# Schematic.net
KiCad netlist of a schematic drawn in EAGLE
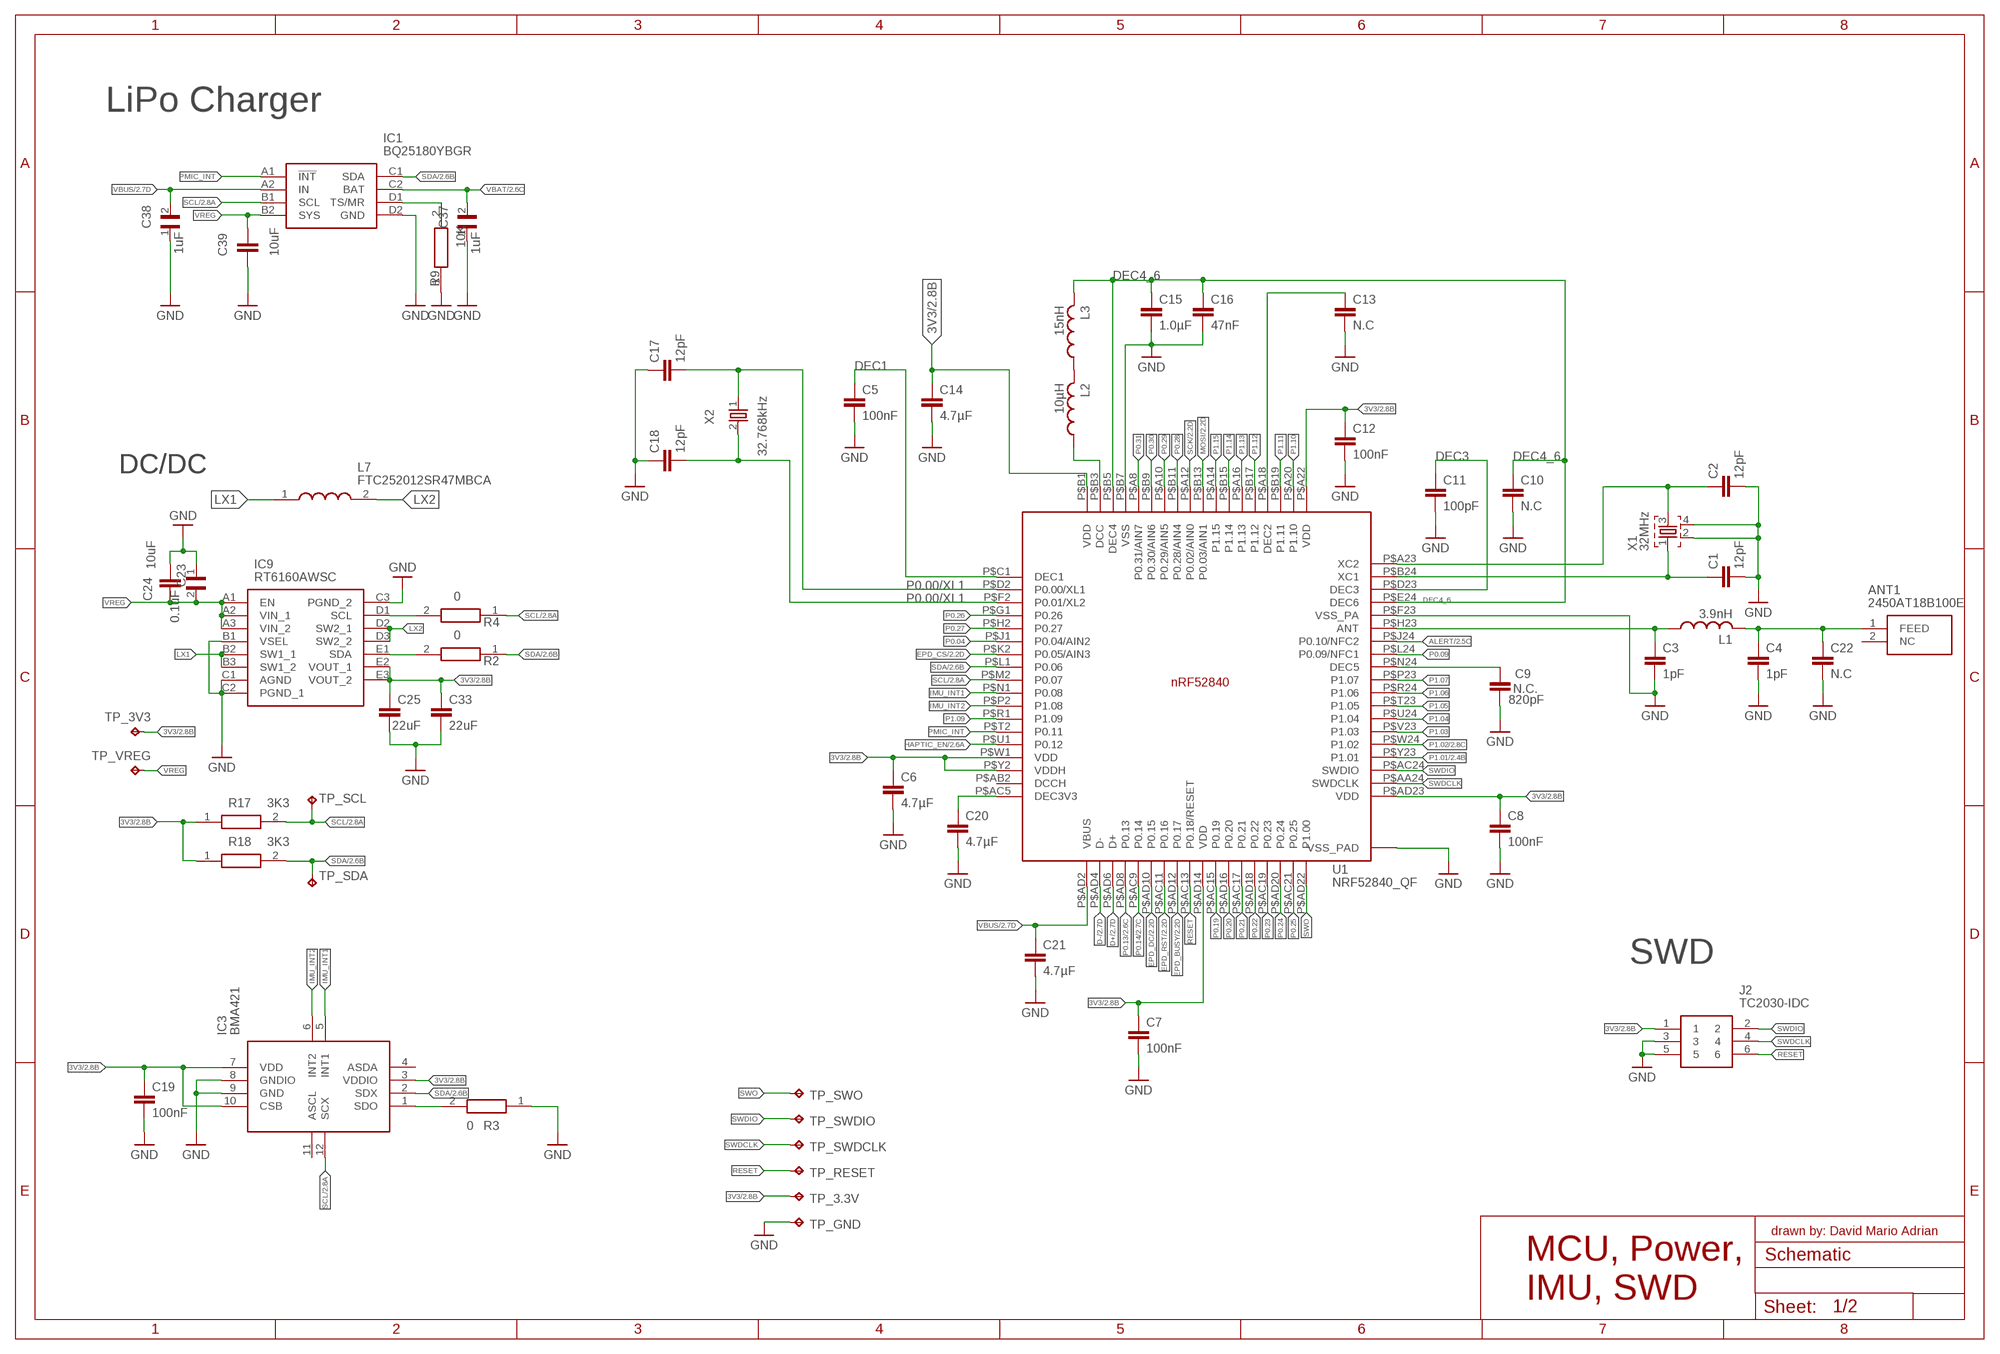
[diagram p0: schematic, sheet 1]
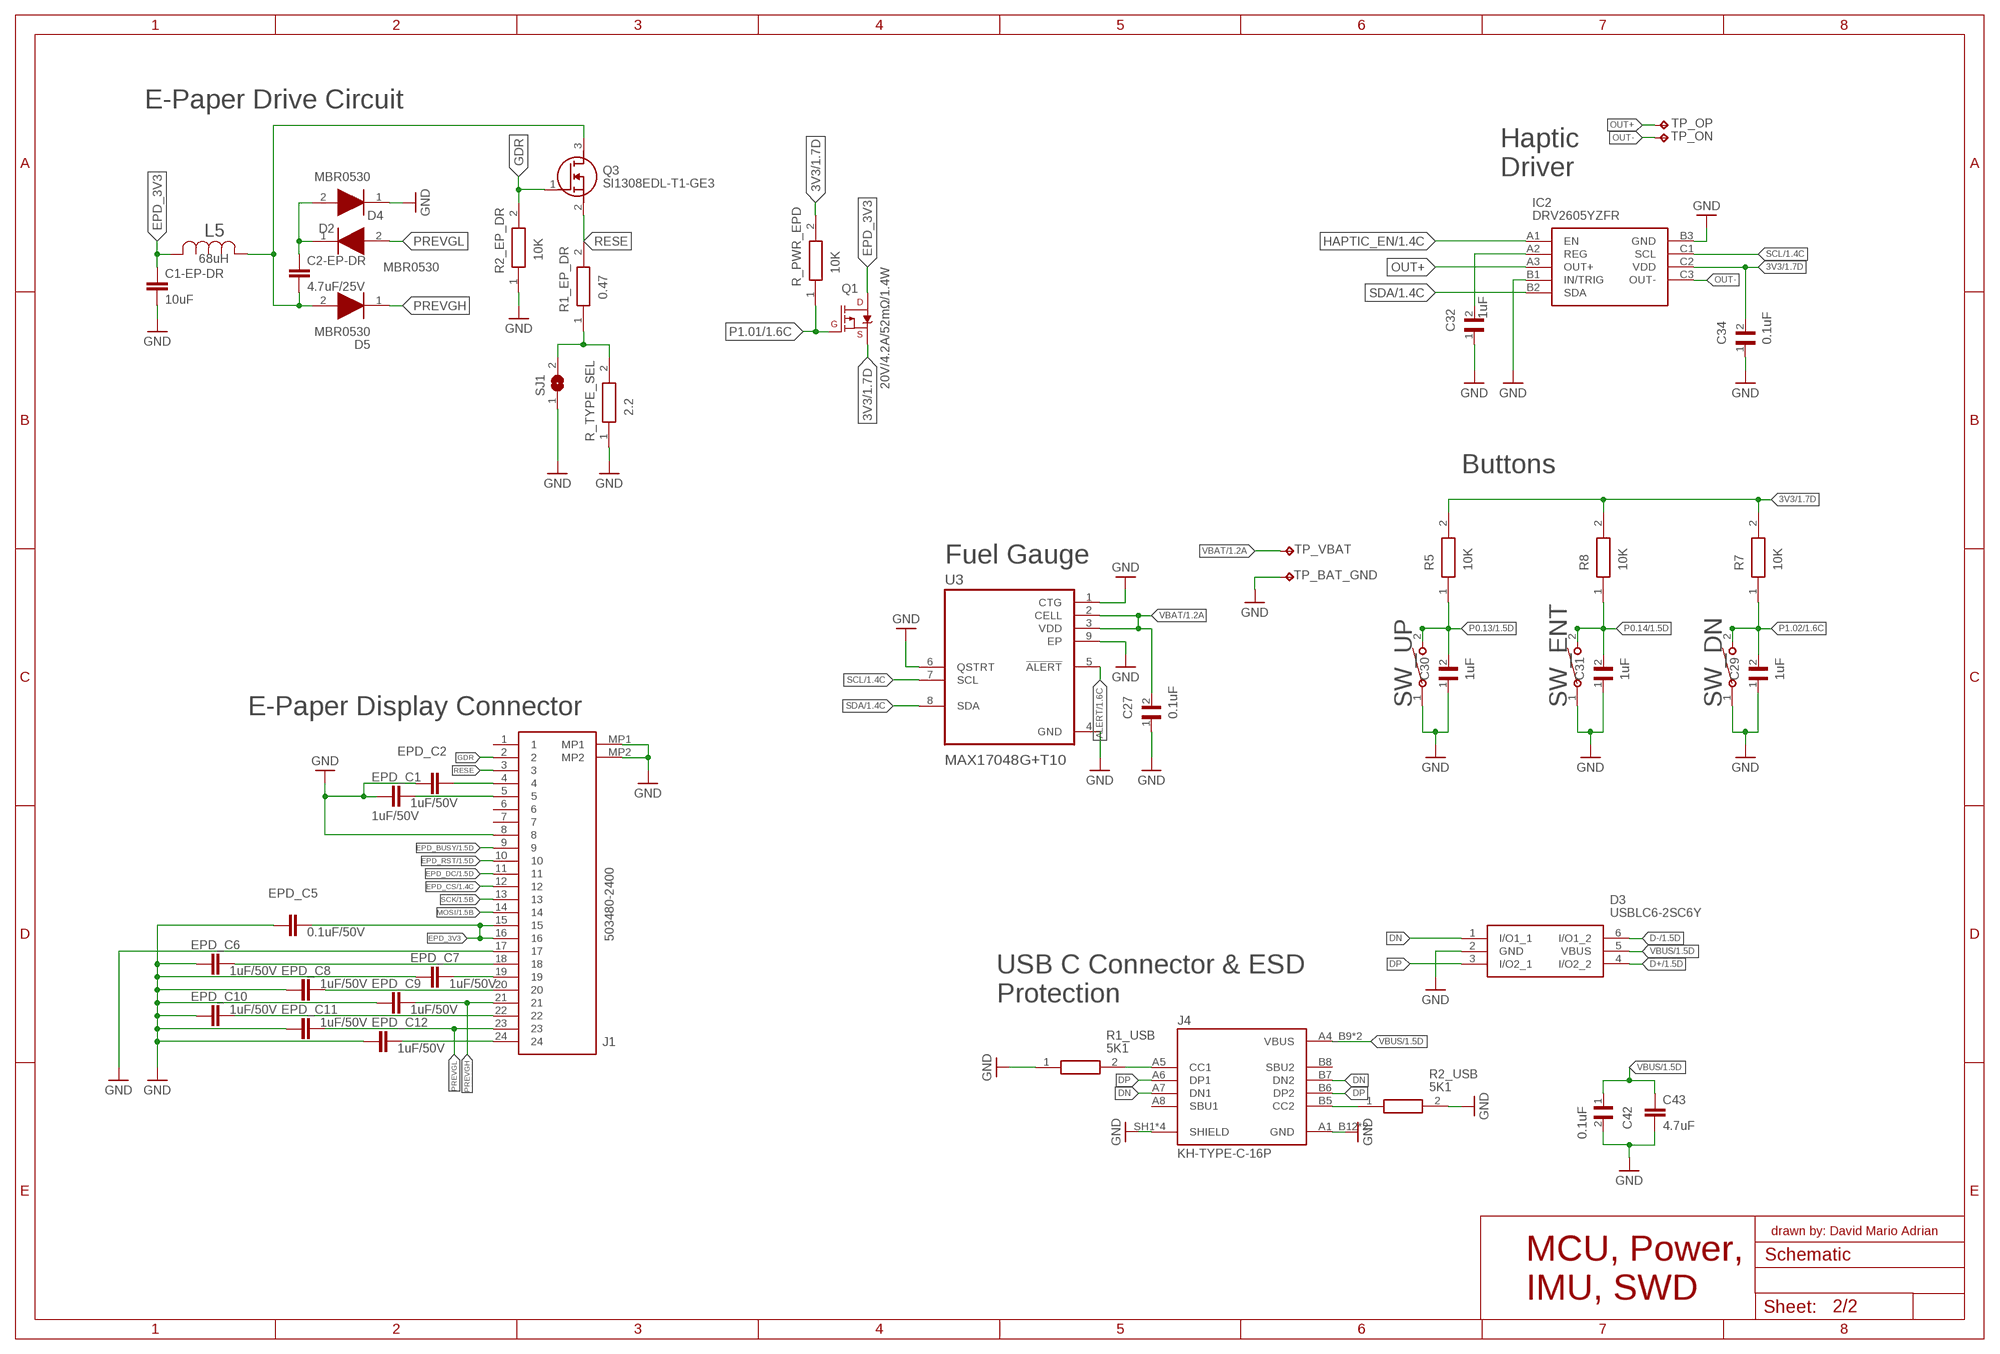
[diagram p1: schematic, sheet 2]

(export (version "E")
  (design (tool "Eeschema 10.0.6"))
  (components
    (comp (ref "C1-EP-DR")
      (value "10uF")
      (footprint "eagle-import:NORDIC_NRF_3_RESC0603_L")
      (libsource (lib "eagle-import") (part "NORDIC_NRF_3_CAPACITOR_0603_L"))
    )
    (comp (ref "C2-EP-DR")
      (value "4.7uF/25V")
      (footprint "eagle-import:NORDIC_NRF_3_RESC0603_L")
      (libsource (lib "eagle-import") (part "NORDIC_NRF_3_CAPACITOR_0603_L"))
    )
    (comp (ref "C27")
      (value "0.1uF")
      (footprint "eagle-import:GRM011R60J152KE01L_2_CAPC0201X13N")
      (fields (field (name "MF") "Murata") (field (name "MP") "GRM011R60J152KE01L"))
      (libsource (lib "eagle-import") (part "GRM011R60J152KE01L_2_GRM011R60J152KE01L"))
    )
    (comp (ref "C29")
      (value "1uF")
      (footprint "eagle-import:GRM011R60J152KE01L_2_CAPC0201X13N")
      (fields (field (name "MF") "Murata") (field (name "MP") "GRM011R60J152KE01L"))
      (libsource (lib "eagle-import") (part "GRM011R60J152KE01L_2_GRM011R60J152KE01L"))
    )
    (comp (ref "C30")
      (value "1uF")
      (footprint "eagle-import:GRM011R60J152KE01L_2_CAPC0201X13N")
      (fields (field (name "MF") "Murata") (field (name "MP") "GRM011R60J152KE01L"))
      (libsource (lib "eagle-import") (part "GRM011R60J152KE01L_2_GRM011R60J152KE01L"))
    )
    (comp (ref "C31")
      (value "1uF")
      (footprint "eagle-import:GRM011R60J152KE01L_2_CAPC0201X13N")
      (fields (field (name "MF") "Murata") (field (name "MP") "GRM011R60J152KE01L"))
      (libsource (lib "eagle-import") (part "GRM011R60J152KE01L_2_GRM011R60J152KE01L"))
    )
    (comp (ref "C32")
      (value "1uF")
      (footprint "eagle-import:GRM011R60J152KE01L_2_CAPC0201X13N")
      (fields (field (name "MF") "Murata") (field (name "MP") "GRM011R60J152KE01L"))
      (libsource (lib "eagle-import") (part "GRM011R60J152KE01L_2_GRM011R60J152KE01L"))
    )
    (comp (ref "C34")
      (value "0.1uF")
      (footprint "eagle-import:GRM011R60J152KE01L_2_CAPC0201X13N")
      (fields (field (name "MF") "Murata") (field (name "MP") "GRM011R60J152KE01L"))
      (libsource (lib "eagle-import") (part "GRM011R60J152KE01L_2_GRM011R60J152KE01L"))
    )
    (comp (ref "C42")
      (value "0.1uF")
      (footprint "eagle-import:GRM011R60J152KE01L_2_CAPC0201X13N")
      (fields (field (name "MF") "Murata") (field (name "MP") "GRM011R60J152KE01L"))
      (libsource (lib "eagle-import") (part "GRM011R60J152KE01L_2_GRM011R60J152KE01L"))
    )
    (comp (ref "C43")
      (value "4.7uF")
      (footprint "eagle-import:PERFECT_0402_0402")
      (libsource (lib "eagle-import") (part "PERFECT_0402_CAP_0402"))
    )
    (comp (ref "D2")
      (value "MBR0530")
      (footprint "eagle-import:ESP32_C6_LIBRARY_5_SOD3716X135N")
      (fields (field (name "MF") "ON Semiconductor"))
      (libsource (lib "eagle-import") (part "ESP32_C6_LIBRARY_5_MBR0530"))
    )
    (comp (ref "D3")
      (value "USBLC6-2SC6Y")
      (footprint "eagle-import:ESP32_C6_LIBRARY_3_SOT95P280X145-6N")
      (fields (field (name "MF") "STMicroelectronics"))
      (libsource (lib "eagle-import") (part "ESP32_C6_LIBRARY_3_USBLC6-2SC6Y"))
    )
    (comp (ref "D4")
      (value "MBR0530")
      (footprint "eagle-import:ESP32_C6_LIBRARY_5_SOD3716X135N")
      (fields (field (name "MF") "ON Semiconductor"))
      (libsource (lib "eagle-import") (part "ESP32_C6_LIBRARY_5_MBR0530"))
    )
    (comp (ref "D5")
      (value "MBR0530")
      (footprint "eagle-import:ESP32_C6_LIBRARY_5_SOD3716X135N")
      (fields (field (name "MF") "ON Semiconductor"))
      (libsource (lib "eagle-import") (part "ESP32_C6_LIBRARY_5_MBR0530"))
    )
    (comp (ref "EPD_C1")
      (value "1uF/50V")
      (footprint "eagle-import:PERFECT_0402_0402")
      (libsource (lib "eagle-import") (part "PERFECT_0402_CAP_0402"))
    )
    (comp (ref "EPD_C2")
      (value "1uF/50V")
      (footprint "eagle-import:PERFECT_0402_0402")
      (libsource (lib "eagle-import") (part "PERFECT_0402_CAP_0402"))
    )
    (comp (ref "EPD_C5")
      (value "0.1uF/50V")
      (footprint "eagle-import:NORDIC_NRF_3_RESC0201_L")
      (libsource (lib "eagle-import") (part "NORDIC_NRF_3_CAPACITOR_0201_L"))
    )
    (comp (ref "EPD_C6")
      (value "1uF/50V")
      (footprint "eagle-import:PERFECT_0402_0402")
      (libsource (lib "eagle-import") (part "PERFECT_0402_CAP_0402"))
    )
    (comp (ref "EPD_C7")
      (value "1uF/50V")
      (footprint "eagle-import:PERFECT_0402_0402")
      (libsource (lib "eagle-import") (part "PERFECT_0402_CAP_0402"))
    )
    (comp (ref "EPD_C8")
      (value "1uF/50V")
      (footprint "eagle-import:PERFECT_0402_0402")
      (libsource (lib "eagle-import") (part "PERFECT_0402_CAP_0402"))
    )
    (comp (ref "EPD_C9")
      (value "1uF/50V")
      (footprint "eagle-import:PERFECT_0402_0402")
      (libsource (lib "eagle-import") (part "PERFECT_0402_CAP_0402"))
    )
    (comp (ref "EPD_C10")
      (value "1uF/50V")
      (footprint "eagle-import:PERFECT_0402_0402")
      (libsource (lib "eagle-import") (part "PERFECT_0402_CAP_0402"))
    )
    (comp (ref "EPD_C11")
      (value "1uF/50V")
      (footprint "eagle-import:PERFECT_0402_0402")
      (libsource (lib "eagle-import") (part "PERFECT_0402_CAP_0402"))
    )
    (comp (ref "EPD_C12")
      (value "1uF/50V")
      (footprint "eagle-import:PERFECT_0402_0402")
      (libsource (lib "eagle-import") (part "PERFECT_0402_CAP_0402"))
    )
    (comp (ref "IC2")
      (value "DRV2605YZFR")
      (footprint "eagle-import:DRV2605YZFR_BGA9C50P3X3_144X144X62")
      (libsource (lib "eagle-import") (part "DRV2605YZFR_DRV2605YZFR"))
    )
    (comp (ref "J1")
      (value "503480-2400")
      (footprint "eagle-import:503480-2400_5034802400")
      (fields (field (name "MOUSER_PART_NUMBER") "538-503480-2400"))
      (libsource (lib "eagle-import") (part "503480-2400_503480-2400"))
    )
    (comp (ref "J4")
      (value "KH-TYPE-C-16P")
      (footprint "eagle-import:KH-TYPE-C-16P_KINGHELM_KH-TYPE-C-16P")
      (fields (field (name "MF") "kinghelm"))
      (libsource (lib "eagle-import") (part "KH-TYPE-C-16P_KH-TYPE-C-16P"))
    )
    (comp (ref "L5")
      (value "68uH")
      (footprint "eagle-import:ESP32_C6_LIBRARY_2_IND_4828-WE-TPC_WRE")
      (fields
        (field (name "MANUFACTURER_PART_NUMBER") "744043680")
        (field (name "COPYRIGHT") "Copyright (C) 2024 Ultra Librarian. All rights reserved.")
      )
      (libsource (lib "eagle-import") (part "ESP32_C6_LIBRARY_2_744043680IND_4828-WE-TPC_WRE"))
    )
    (comp (ref "Q1")
      (value "20V/4.2A/52mΩ/1.4W")
      (footprint "eagle-import:ESP32_C6_LIBRARY_4_ESP32_C6_LIBRARY_4_ESP32_C6_LIBRARY_4_ESP32_C6_LIBRARY_4_ESP32_WROVER_SPARKFUN-DISCRETESEMI_SOT23-3")
      (libsource (lib "eagle-import") (part "ESP32_C6_LIBRARY_4_ESP32_WROVER_SPARKFUN-DISCRETESEMI_MOSFET_PCH-DMG2305UX-7"))
    )
    (comp (ref "Q3")
      (value "SI1308EDL-T1-GE3")
      (footprint "eagle-import:ESP32_C6_LIBRARY_6_SOT65P210X110-3N")
      (fields (field (name "MF") "Vishay Siliconix"))
      (libsource (lib "eagle-import") (part "ESP32_C6_LIBRARY_6_SI1308EDL-T1-GE3"))
    )
    (comp (ref "R1_EP_DR")
      (value "0.47")
      (footprint "eagle-import:CPF0201D7K68C1_0201")
      (libsource (lib "eagle-import") (part "CPF0201D7K68C1_CPF0201D7K68C1"))
    )
    (comp (ref "R1_USB")
      (value "5K1")
      (footprint "eagle-import:CPF0201D7K68C1_0201")
      (libsource (lib "eagle-import") (part "CPF0201D7K68C1_CPF0201D7K68C1"))
    )
    (comp (ref "R2_EP_DR")
      (value "10K")
      (footprint "eagle-import:CPF0201D7K68C1_0201")
      (libsource (lib "eagle-import") (part "CPF0201D7K68C1_CPF0201D7K68C1"))
    )
    (comp (ref "R2_USB")
      (value "5K1")
      (footprint "eagle-import:CPF0201D7K68C1_0201")
      (libsource (lib "eagle-import") (part "CPF0201D7K68C1_CPF0201D7K68C1"))
    )
    (comp (ref "R5")
      (value "10K")
      (footprint "eagle-import:CPF0201D7K68C1_0201")
      (libsource (lib "eagle-import") (part "CPF0201D7K68C1_CPF0201D7K68C1"))
    )
    (comp (ref "R7")
      (value "10K")
      (footprint "eagle-import:CPF0201D7K68C1_0201")
      (libsource (lib "eagle-import") (part "CPF0201D7K68C1_CPF0201D7K68C1"))
    )
    (comp (ref "R8")
      (value "10K")
      (footprint "eagle-import:CPF0201D7K68C1_0201")
      (libsource (lib "eagle-import") (part "CPF0201D7K68C1_CPF0201D7K68C1"))
    )
    (comp (ref "R_PWR_EPD")
      (value "10K")
      (footprint "eagle-import:CPF0201D7K68C1_0201")
      (libsource (lib "eagle-import") (part "CPF0201D7K68C1_CPF0201D7K68C1"))
    )
    (comp (ref "R_TYPE_SEL")
      (value "2.2")
      (footprint "eagle-import:CPF0201D7K68C1_0201")
      (libsource (lib "eagle-import") (part "CPF0201D7K68C1_CPF0201D7K68C1"))
    )
    (comp (ref "SJ1")
      (value "ESP32_C6_LIBRARY_7_JUMPER_SJ")
      (footprint "eagle-import:ESP32_C6_LIBRARY_7_JUMPER_SJ")
      (libsource (lib "eagle-import") (part "ESP32_C6_LIBRARY_7_JUMPER_SJ"))
    )
    (comp (ref "SW_DN")
      (value "2025-10-22_07-23-44_LIBRARY_EVP-AKE31ASW_EVP-AKE31A_PAN")
      (footprint "eagle-import:2025-10-22_07-23-44_LIBRARY_SW_EVP-AKE31A_PAN")
      (fields
        (field (name "MANUFACTURER_PART_NUMBER") "EVP-AKE31A")
        (field (name "COPYRIGHT") "Copyright (C) 2025 Ultra Librarian. All rights reserved.")
      )
      (libsource (lib "eagle-import") (part "2025-10-22_07-23-44_LIBRARY_EVP-AKE31ASW_EVP-AKE31A_PAN"))
    )
    (comp (ref "SW_ENT")
      (value "2025-10-22_07-23-44_LIBRARY_EVP-AKE31ASW_EVP-AKE31A_PAN")
      (footprint "eagle-import:2025-10-22_07-23-44_LIBRARY_SW_EVP-AKE31A_PAN")
      (fields
        (field (name "MANUFACTURER_PART_NUMBER") "EVP-AKE31A")
        (field (name "COPYRIGHT") "Copyright (C) 2025 Ultra Librarian. All rights reserved.")
      )
      (libsource (lib "eagle-import") (part "2025-10-22_07-23-44_LIBRARY_EVP-AKE31ASW_EVP-AKE31A_PAN"))
    )
    (comp (ref "SW_UP")
      (value "2025-10-22_07-23-44_LIBRARY_EVP-AKE31ASW_EVP-AKE31A_PAN")
      (footprint "eagle-import:2025-10-22_07-23-44_LIBRARY_SW_EVP-AKE31A_PAN")
      (fields
        (field (name "MANUFACTURER_PART_NUMBER") "EVP-AKE31A")
        (field (name "COPYRIGHT") "Copyright (C) 2025 Ultra Librarian. All rights reserved.")
      )
      (libsource (lib "eagle-import") (part "2025-10-22_07-23-44_LIBRARY_EVP-AKE31ASW_EVP-AKE31A_PAN"))
    )
    (comp (ref "TP_BAT_GND")
      (value "HECTOR_WATCH_1_TPTP20R")
      (footprint "eagle-import:HECTOR_WATCH_1_TP20R")
      (libsource (lib "eagle-import") (part "HECTOR_WATCH_1_TPTP20R"))
    )
    (comp (ref "TP_ON")
      (value "HECTOR_WATCH_1_TPTP20R")
      (footprint "eagle-import:HECTOR_WATCH_1_TP20R")
      (libsource (lib "eagle-import") (part "HECTOR_WATCH_1_TPTP20R"))
    )
    (comp (ref "TP_OP")
      (value "HECTOR_WATCH_1_TPTP20R")
      (footprint "eagle-import:HECTOR_WATCH_1_TP20R")
      (libsource (lib "eagle-import") (part "HECTOR_WATCH_1_TPTP20R"))
    )
    (comp (ref "TP_VBAT")
      (value "HECTOR_WATCH_1_TPTP20R")
      (footprint "eagle-import:HECTOR_WATCH_1_TP20R")
      (libsource (lib "eagle-import") (part "HECTOR_WATCH_1_TPTP20R"))
    )
    (comp (ref "U3")
      (value "MAX17048G+T10")
      (footprint "eagle-import:ESP32_C6_LIBRARY_SON50P200X200X80-9N")
      (fields (field (name "MF") "Analog Devices"))
      (libsource (lib "eagle-import") (part "ESP32_C6_LIBRARY_MAX17048G+T10"))
    )
    (comp (ref "ANT1")
      (value "2450AT18B100E")
      (footprint "eagle-import:2450AT18B100E_ANTC3216X140N")
      (fields (field (name "MOUSER_PART_NUMBER") "609-2450AT18B100E"))
      (libsource (lib "eagle-import") (part "2450AT18B100E_2450AT18B100E"))
    )
    (comp (ref "C1")
      (value "12pF")
      (footprint "eagle-import:NORDIC_NRF_3_RESC0201_L")
      (libsource (lib "eagle-import") (part "NORDIC_NRF_3_CAPACITOR_0201_L"))
    )
    (comp (ref "C2")
      (value "12pF")
      (footprint "eagle-import:NORDIC_NRF_3_RESC0201_L")
      (libsource (lib "eagle-import") (part "NORDIC_NRF_3_CAPACITOR_0201_L"))
    )
    (comp (ref "C3")
      (value "1pF")
      (footprint "eagle-import:NORDIC_NRF_3_RESC0201_L")
      (libsource (lib "eagle-import") (part "NORDIC_NRF_3_CAPACITOR_0201_L"))
    )
    (comp (ref "C4")
      (value "1pF")
      (footprint "eagle-import:NORDIC_NRF_3_RESC0201_L")
      (libsource (lib "eagle-import") (part "NORDIC_NRF_3_CAPACITOR_0201_L"))
    )
    (comp (ref "C5")
      (value "100nF")
      (footprint "eagle-import:NORDIC_NRF_3_RESC0201_L")
      (libsource (lib "eagle-import") (part "NORDIC_NRF_3_CAPACITOR_0201_L"))
    )
    (comp (ref "C6")
      (value "4.7µF")
      (footprint "eagle-import:PERFECT_0402_0402")
      (libsource (lib "eagle-import") (part "PERFECT_0402_CAP_0402"))
    )
    (comp (ref "C7")
      (value "100nF")
      (footprint "eagle-import:NORDIC_NRF_3_RESC0201_L")
      (libsource (lib "eagle-import") (part "NORDIC_NRF_3_CAPACITOR_0201_L"))
    )
    (comp (ref "C8")
      (value "100nF")
      (footprint "eagle-import:NORDIC_NRF_3_RESC0201_L")
      (libsource (lib "eagle-import") (part "NORDIC_NRF_3_CAPACITOR_0201_L"))
    )
    (comp (ref "C9")
      (value "820pF")
      (footprint "eagle-import:NORDIC_NRF_3_RESC0201_L")
      (libsource (lib "eagle-import") (part "NORDIC_NRF_3_CAPACITOR_0201_L"))
    )
    (comp (ref "C10")
      (value "N.C")
      (footprint "eagle-import:NORDIC_NRF_3_RESC0201_L")
      (libsource (lib "eagle-import") (part "NORDIC_NRF_3_CAPACITOR_0201_L"))
    )
    (comp (ref "C11")
      (value "100pF")
      (footprint "eagle-import:NORDIC_NRF_3_RESC0201_L")
      (libsource (lib "eagle-import") (part "NORDIC_NRF_3_CAPACITOR_0201_L"))
    )
    (comp (ref "C12")
      (value "100nF")
      (footprint "eagle-import:NORDIC_NRF_3_RESC0201_L")
      (libsource (lib "eagle-import") (part "NORDIC_NRF_3_CAPACITOR_0201_L"))
    )
    (comp (ref "C13")
      (value "N.C")
      (footprint "eagle-import:NORDIC_NRF_3_RESC0201_L")
      (libsource (lib "eagle-import") (part "NORDIC_NRF_3_CAPACITOR_0201_L"))
    )
    (comp (ref "C14")
      (value "4.7µF")
      (footprint "eagle-import:PERFECT_0402_0402")
      (libsource (lib "eagle-import") (part "PERFECT_0402_CAP_0402"))
    )
    (comp (ref "C15")
      (value "1.0µF")
      (footprint "eagle-import:PERFECT_0402_0402")
      (libsource (lib "eagle-import") (part "PERFECT_0402_CAP_0402"))
    )
    (comp (ref "C16")
      (value "47nF")
      (footprint "eagle-import:NORDIC_NRF_3_RESC0201_L")
      (libsource (lib "eagle-import") (part "NORDIC_NRF_3_CAPACITOR_0201_L"))
    )
    (comp (ref "C17")
      (value "12pF")
      (footprint "eagle-import:NORDIC_NRF_3_RESC0201_L")
      (libsource (lib "eagle-import") (part "NORDIC_NRF_3_CAPACITOR_0201_L"))
    )
    (comp (ref "C18")
      (value "12pF")
      (footprint "eagle-import:NORDIC_NRF_3_RESC0201_L")
      (libsource (lib "eagle-import") (part "NORDIC_NRF_3_CAPACITOR_0201_L"))
    )
    (comp (ref "C19")
      (value "100nF")
      (footprint "eagle-import:NORDIC_NRF_3_RESC0201_L")
      (libsource (lib "eagle-import") (part "NORDIC_NRF_3_CAPACITOR_0201_L"))
    )
    (comp (ref "C20")
      (value "4.7µF")
      (footprint "eagle-import:PERFECT_0402_0402")
      (libsource (lib "eagle-import") (part "PERFECT_0402_CAP_0402"))
    )
    (comp (ref "C21")
      (value "4.7µF")
      (footprint "eagle-import:PERFECT_0402_0402")
      (libsource (lib "eagle-import") (part "PERFECT_0402_CAP_0402"))
    )
    (comp (ref "C22")
      (value "N.C")
      (footprint "eagle-import:NORDIC_NRF_3_RESC0201_L")
      (libsource (lib "eagle-import") (part "NORDIC_NRF_3_CAPACITOR_0201_L"))
    )
    (comp (ref "C23")
      (value "0.1uF")
      (footprint "eagle-import:GRM011R60J152KE01L_2_CAPC0201X13N")
      (fields (field (name "MF") "Murata") (field (name "MP") "GRM011R60J152KE01L"))
      (libsource (lib "eagle-import") (part "GRM011R60J152KE01L_2_GRM011R60J152KE01L"))
    )
    (comp (ref "C24")
      (value "10uF")
      (footprint "eagle-import:PERFECT_0402_0402")
      (libsource (lib "eagle-import") (part "PERFECT_0402_CAP_0402"))
    )
    (comp (ref "C25")
      (value "22uF")
      (footprint "eagle-import:PERFECT_0402_0402")
      (libsource (lib "eagle-import") (part "PERFECT_0402_CAP_0402"))
    )
    (comp (ref "C33")
      (value "22uF")
      (footprint "eagle-import:PERFECT_0402_0402")
      (libsource (lib "eagle-import") (part "PERFECT_0402_CAP_0402"))
    )
    (comp (ref "C37")
      (value "1uF")
      (footprint "eagle-import:GRM011R60J152KE01L_2_CAPC0201X13N")
      (fields (field (name "MF") "Murata") (field (name "MP") "GRM011R60J152KE01L"))
      (libsource (lib "eagle-import") (part "GRM011R60J152KE01L_2_GRM011R60J152KE01L"))
    )
    (comp (ref "C38")
      (value "1uF")
      (footprint "eagle-import:GRM011R60J152KE01L_2_CAPC0201X13N")
      (fields (field (name "MF") "Murata") (field (name "MP") "GRM011R60J152KE01L"))
      (libsource (lib "eagle-import") (part "GRM011R60J152KE01L_2_GRM011R60J152KE01L"))
    )
    (comp (ref "C39")
      (value "10uF")
      (footprint "eagle-import:PERFECT_0402_0402")
      (libsource (lib "eagle-import") (part "PERFECT_0402_CAP_0402"))
    )
    (comp (ref "IC1")
      (value "BQ25180YBGR")
      (footprint "eagle-import:BQ25180YBGR_BGA8C40P2X4_100X155X50")
      (fields (field (name "MOUSER_PART_NUMBER") "595-BQ25180YBGR"))
      (libsource (lib "eagle-import") (part "BQ25180YBGR_BQ25180YBGR"))
    )
    (comp (ref "IC3")
      (value "BMA421")
      (footprint "eagle-import:BMA423_BMA423")
      (fields (field (name "ARROW_PART_NUMBER") "BMA423") (field (name "MOUSER_PART_NUMBER") "262-BMA423"))
      (libsource (lib "eagle-import") (part "BMA423_BMA423"))
    )
    (comp (ref "IC9")
      (value "RT6160AWSC")
      (footprint "eagle-import:RT6160AWSC_BGA15C40P3X5_140X230X60")
      (fields (field (name "MOUSER_PART_NUMBER") "835-RT6160AWSC"))
      (libsource (lib "eagle-import") (part "RT6160AWSC_RT6160AWSC"))
    )
    (comp (ref "J2")
      (value "TC2030-IDC")
      (footprint "eagle-import:TC2030-IDC_TC2030IDC")
      (libsource (lib "eagle-import") (part "TC2030-IDC_TC2030-IDC"))
    )
    (comp (ref "L1")
      (value "3.9nH")
      (footprint "eagle-import:NORDIC_NRF_2_RESC0402_L")
      (libsource (lib "eagle-import") (part "NORDIC_NRF_2_INDUCTOR_0402_L"))
    )
    (comp (ref "L2")
      (value "10µH")
      (footprint "eagle-import:NORDIC_NRF_2_RESC0402_L")
      (libsource (lib "eagle-import") (part "NORDIC_NRF_2_INDUCTOR_0402_L"))
    )
    (comp (ref "L3")
      (value "15nH")
      (footprint "eagle-import:NORDIC_NRF_2_RESC0402_L")
      (libsource (lib "eagle-import") (part "NORDIC_NRF_2_INDUCTOR_0402_L"))
    )
    (comp (ref "L7")
      (value "FTC252012SR47MBCA")
      (footprint "eagle-import:MLP2016SR47MT0S1_INDC2016X100N")
      (libsource (lib "eagle-import") (part "MLP2016SR47MT0S1_FTC252012SR47MBCA"))
    )
    (comp (ref "R2")
      (value "0")
      (footprint "eagle-import:CPF0201D7K68C1_0201")
      (libsource (lib "eagle-import") (part "CPF0201D7K68C1_CPF0201D7K68C1"))
    )
    (comp (ref "R3")
      (value "0")
      (footprint "eagle-import:CPF0201D7K68C1_0201")
      (libsource (lib "eagle-import") (part "CPF0201D7K68C1_CPF0201D7K68C1"))
    )
    (comp (ref "R4")
      (value "0")
      (footprint "eagle-import:CPF0201D7K68C1_0201")
      (libsource (lib "eagle-import") (part "CPF0201D7K68C1_CPF0201D7K68C1"))
    )
    (comp (ref "R9")
      (value "10K")
      (footprint "eagle-import:CPF0201D7K68C1_0201")
      (libsource (lib "eagle-import") (part "CPF0201D7K68C1_CPF0201D7K68C1"))
    )
    (comp (ref "R17")
      (value "3K3")
      (footprint "eagle-import:CPF0201D7K68C1_0201")
      (libsource (lib "eagle-import") (part "CPF0201D7K68C1_CPF0201D7K68C1"))
    )
    (comp (ref "R18")
      (value "3K3")
      (footprint "eagle-import:CPF0201D7K68C1_0201")
      (libsource (lib "eagle-import") (part "CPF0201D7K68C1_CPF0201D7K68C1"))
    )
    (comp (ref "TP_3.3V")
      (value "HECTOR_WATCH_1_TPTP20R")
      (footprint "eagle-import:HECTOR_WATCH_1_TP20R")
      (libsource (lib "eagle-import") (part "HECTOR_WATCH_1_TPTP20R"))
    )
    (comp (ref "TP_3V3")
      (value "HECTOR_WATCH_1_TPTP20R")
      (footprint "eagle-import:HECTOR_WATCH_1_TP20R")
      (libsource (lib "eagle-import") (part "HECTOR_WATCH_1_TPTP20R"))
    )
    (comp (ref "TP_GND")
      (value "HECTOR_WATCH_1_TPTP20R")
      (footprint "eagle-import:HECTOR_WATCH_1_TP20R")
      (libsource (lib "eagle-import") (part "HECTOR_WATCH_1_TPTP20R"))
    )
    (comp (ref "TP_RESET")
      (value "HECTOR_WATCH_1_TPTP20R")
      (footprint "eagle-import:HECTOR_WATCH_1_TP20R")
      (libsource (lib "eagle-import") (part "HECTOR_WATCH_1_TPTP20R"))
    )
    (comp (ref "TP_SCL")
      (value "HECTOR_WATCH_1_TPTP20R")
      (footprint "eagle-import:HECTOR_WATCH_1_TP20R")
      (libsource (lib "eagle-import") (part "HECTOR_WATCH_1_TPTP20R"))
    )
    (comp (ref "TP_SDA")
      (value "HECTOR_WATCH_1_TPTP20R")
      (footprint "eagle-import:HECTOR_WATCH_1_TP20R")
      (libsource (lib "eagle-import") (part "HECTOR_WATCH_1_TPTP20R"))
    )
    (comp (ref "TP_SWDCLK")
      (value "HECTOR_WATCH_1_TPTP20R")
      (footprint "eagle-import:HECTOR_WATCH_1_TP20R")
      (libsource (lib "eagle-import") (part "HECTOR_WATCH_1_TPTP20R"))
    )
    (comp (ref "TP_SWDIO")
      (value "HECTOR_WATCH_1_TPTP20R")
      (footprint "eagle-import:HECTOR_WATCH_1_TP20R")
      (libsource (lib "eagle-import") (part "HECTOR_WATCH_1_TPTP20R"))
    )
    (comp (ref "TP_SWO")
      (value "HECTOR_WATCH_1_TPTP20R")
      (footprint "eagle-import:HECTOR_WATCH_1_TP20R")
      (libsource (lib "eagle-import") (part "HECTOR_WATCH_1_TPTP20R"))
    )
    (comp (ref "TP_VREG")
      (value "HECTOR_WATCH_1_TPTP20R")
      (footprint "eagle-import:HECTOR_WATCH_1_TP20R")
      (libsource (lib "eagle-import") (part "HECTOR_WATCH_1_TPTP20R"))
    )
    (comp (ref "U1")
      (value "NRF52840_QF")
      (footprint "eagle-import:NORDIC_NRF_4_AQFN50P700X700X85_HS-74N")
      (libsource (lib "eagle-import") (part "NORDIC_NRF_4_NRF52840_QF"))
    )
    (comp (ref "X1")
      (value "32MHz")
      (footprint "eagle-import:NORDIC_NRF_BT-XTAL_2016_N")
      (libsource (lib "eagle-import") (part "NORDIC_NRF_XTAL_32MHZ"))
    )
    (comp (ref "X2")
      (value "32.768kHz")
      (footprint "eagle-import:NORDIC_NRF_1_XTAL_3215_N")
      (libsource (lib "eagle-import") (part "NORDIC_NRF_1_XTAL_32KHZ"))
    )
  )
  (nets
    (net (code "1") (name "3V3") (class "Default")
      (node (ref "C12") (pin "1") (pinfunction "1_1") (pintype "passive"))
      (node (ref "C14") (pin "1") (pinfunction "1_1") (pintype "passive"))
      (node (ref "C19") (pin "1") (pinfunction "1_1") (pintype "passive"))
      (node (ref "C25") (pin "2") (pinfunction "2_2") (pintype "passive"))
      (node (ref "C33") (pin "1") (pinfunction "1_1") (pintype "passive"))
      (node (ref "C34") (pin "2") (pinfunction "2_2") (pintype "passive"))
      (node (ref "C6") (pin "1") (pinfunction "1_1") (pintype "passive"))
      (node (ref "C7") (pin "1") (pinfunction "1_1") (pintype "passive"))
      (node (ref "C8") (pin "1") (pinfunction "1_1") (pintype "passive"))
      (node (ref "IC2") (pin "C2") (pinfunction "VDD_C2") (pintype "bidirectional"))
      (node (ref "IC3") (pin "10") (pinfunction "CSB_10") (pintype "bidirectional"))
      (node (ref "IC3") (pin "3") (pinfunction "VDDIO_3") (pintype "bidirectional"))
      (node (ref "IC3") (pin "7") (pinfunction "VDD_7") (pintype "bidirectional"))
      (node (ref "IC9") (pin "E2") (pinfunction "VOUT_1_E2") (pintype "bidirectional"))
      (node (ref "IC9") (pin "E3") (pinfunction "VOUT_2_E3") (pintype "bidirectional"))
      (node (ref "J2") (pin "1") (pinfunction "1_1") (pintype "bidirectional"))
      (node (ref "Q1") (pin "2") (pinfunction "S_2") (pintype "bidirectional"))
      (node (ref "R17") (pin "1") (pinfunction "1_1") (pintype "bidirectional"))
      (node (ref "R18") (pin "1") (pinfunction "1_1") (pintype "bidirectional"))
      (node (ref "R5") (pin "2") (pinfunction "2_2") (pintype "bidirectional"))
      (node (ref "R7") (pin "2") (pinfunction "2_2") (pintype "bidirectional"))
      (node (ref "R8") (pin "2") (pinfunction "2_2") (pintype "bidirectional"))
      (node (ref "R_PWR_EPD") (pin "2") (pinfunction "2_2") (pintype "bidirectional"))
      (node (ref "TP_3.3V") (pin "TP") (pinfunction "TP_TP") (pintype "input"))
      (node (ref "TP_3V3") (pin "TP") (pinfunction "TP_TP") (pintype "input"))
      (node (ref "U1") (pin "P$A22") (pinfunction "VDD_P$A22") (pintype "power_in"))
      (node (ref "U1") (pin "P$AD14") (pinfunction "VDD_P$AD14") (pintype "power_in"))
      (node (ref "U1") (pin "P$AD23") (pinfunction "VDD_P$AD23") (pintype "power_in"))
      (node (ref "U1") (pin "P$B1") (pinfunction "VDD_P$B1") (pintype "power_in"))
      (node (ref "U1") (pin "P$W1") (pinfunction "VDD_P$W1") (pintype "power_in"))
      (node (ref "U1") (pin "P$Y2") (pinfunction "VDDH_P$Y2") (pintype "power_in"))
    )
    (net (code "2") (name "ALERT") (class "Default")
      (node (ref "U1") (pin "P$J24") (pinfunction "P0.10/NFC2_P$J24") (pintype "bidirectional"))
      (node (ref "U3") (pin "5") (pinfunction "~{ALERT}_5") (pintype "output"))
    )
    (net (code "3") (name "D+") (class "Default")
      (node (ref "D3") (pin "4") (pinfunction "I/O2_2_4") (pintype "bidirectional"))
      (node (ref "U1") (pin "P$AD6") (pinfunction "D+_P$AD6") (pintype "bidirectional"))
    )
    (net (code "4") (name "D-") (class "Default")
      (node (ref "D3") (pin "6") (pinfunction "I/O1_2_6") (pintype "bidirectional"))
      (node (ref "U1") (pin "P$AD4") (pinfunction "D-_P$AD4") (pintype "bidirectional"))
    )
    (net (code "5") (name "DN") (class "Default")
      (node (ref "D3") (pin "1") (pinfunction "I/O1_1_1") (pintype "bidirectional"))
      (node (ref "J4") (pin "A7") (pinfunction "DN1_A7") (pintype "bidirectional"))
      (node (ref "J4") (pin "B7") (pinfunction "DN2_B7") (pintype "bidirectional"))
    )
    (net (code "6") (name "DP") (class "Default")
      (node (ref "D3") (pin "3") (pinfunction "I/O2_1_3") (pintype "bidirectional"))
      (node (ref "J4") (pin "A6") (pinfunction "DP1_A6") (pintype "bidirectional"))
      (node (ref "J4") (pin "B6") (pinfunction "DP2_B6") (pintype "bidirectional"))
    )
    (net (code "7") (name "EPD_3V3") (class "Default")
      (node (ref "C1-EP-DR") (pin "1") (pinfunction "1_1") (pintype "passive"))
      (node (ref "EPD_C5") (pin "1") (pinfunction "1_1") (pintype "passive"))
      (node (ref "J1") (pin "15") (pinfunction "15_15") (pintype "bidirectional"))
      (node (ref "J1") (pin "16") (pinfunction "16_16") (pintype "bidirectional"))
      (node (ref "L5") (pin "2") (pinfunction "2_2") (pintype "passive"))
      (node (ref "Q1") (pin "3") (pinfunction "D_3") (pintype "bidirectional"))
    )
    (net (code "8") (name "EPD_BUSY") (class "Default")
      (node (ref "J1") (pin "9") (pinfunction "9_9") (pintype "bidirectional"))
      (node (ref "U1") (pin "P$AD12") (pinfunction "P0.17_P$AD12") (pintype "bidirectional"))
    )
    (net (code "9") (name "EPD_CS") (class "Default")
      (node (ref "J1") (pin "12") (pinfunction "12_12") (pintype "bidirectional"))
      (node (ref "U1") (pin "P$K2") (pinfunction "P0.05/AIN3_P$K2") (pintype "bidirectional"))
    )
    (net (code "10") (name "EPD_DC") (class "Default")
      (node (ref "J1") (pin "11") (pinfunction "11_11") (pintype "bidirectional"))
      (node (ref "U1") (pin "P$AD10") (pinfunction "P0.15_P$AD10") (pintype "bidirectional"))
    )
    (net (code "11") (name "EPD_RST") (class "Default")
      (node (ref "J1") (pin "10") (pinfunction "10_10") (pintype "bidirectional"))
      (node (ref "U1") (pin "P$AC11") (pinfunction "P0.16_P$AC11") (pintype "bidirectional"))
    )
    (net (code "12") (name "GDR") (class "Default")
      (node (ref "J1") (pin "2") (pinfunction "2_2") (pintype "bidirectional"))
      (node (ref "Q3") (pin "1") (pinfunction "G_1") (pintype "bidirectional"))
      (node (ref "R2_EP_DR") (pin "2") (pinfunction "2_2") (pintype "bidirectional"))
    )
    (net (code "13") (name "GND") (class "Default")
      (node (ref "C1") (pin "2") (pinfunction "2_2") (pintype "passive"))
      (node (ref "C1-EP-DR") (pin "2") (pinfunction "2_2") (pintype "passive"))
      (node (ref "C10") (pin "2") (pinfunction "2_2") (pintype "passive"))
      (node (ref "C11") (pin "2") (pinfunction "2_2") (pintype "passive"))
      (node (ref "C12") (pin "2") (pinfunction "2_2") (pintype "passive"))
      (node (ref "C13") (pin "2") (pinfunction "2_2") (pintype "passive"))
      (node (ref "C14") (pin "2") (pinfunction "2_2") (pintype "passive"))
      (node (ref "C15") (pin "2") (pinfunction "2_2") (pintype "passive"))
      (node (ref "C16") (pin "2") (pinfunction "2_2") (pintype "passive"))
      (node (ref "C17") (pin "1") (pinfunction "1_1") (pintype "passive"))
      (node (ref "C18") (pin "1") (pinfunction "1_1") (pintype "passive"))
      (node (ref "C19") (pin "2") (pinfunction "2_2") (pintype "passive"))
      (node (ref "C2") (pin "2") (pinfunction "2_2") (pintype "passive"))
      (node (ref "C20") (pin "2") (pinfunction "2_2") (pintype "passive"))
      (node (ref "C21") (pin "2") (pinfunction "2_2") (pintype "passive"))
      (node (ref "C22") (pin "2") (pinfunction "2_2") (pintype "passive"))
      (node (ref "C23") (pin "1") (pinfunction "1_1") (pintype "passive"))
      (node (ref "C24") (pin "1") (pinfunction "1_1") (pintype "passive"))
      (node (ref "C25") (pin "1") (pinfunction "1_1") (pintype "passive"))
      (node (ref "C27") (pin "1") (pinfunction "1_1") (pintype "passive"))
      (node (ref "C29") (pin "1") (pinfunction "1_1") (pintype "passive"))
      (node (ref "C3") (pin "2") (pinfunction "2_2") (pintype "passive"))
      (node (ref "C30") (pin "1") (pinfunction "1_1") (pintype "passive"))
      (node (ref "C31") (pin "1") (pinfunction "1_1") (pintype "passive"))
      (node (ref "C32") (pin "1") (pinfunction "1_1") (pintype "passive"))
      (node (ref "C33") (pin "2") (pinfunction "2_2") (pintype "passive"))
      (node (ref "C34") (pin "1") (pinfunction "1_1") (pintype "passive"))
      (node (ref "C37") (pin "1") (pinfunction "1_1") (pintype "passive"))
      (node (ref "C38") (pin "1") (pinfunction "1_1") (pintype "passive"))
      (node (ref "C39") (pin "1") (pinfunction "1_1") (pintype "passive"))
      (node (ref "C4") (pin "2") (pinfunction "2_2") (pintype "passive"))
      (node (ref "C42") (pin "2") (pinfunction "2_2") (pintype "passive"))
      (node (ref "C43") (pin "2") (pinfunction "2_2") (pintype "passive"))
      (node (ref "C5") (pin "2") (pinfunction "2_2") (pintype "passive"))
      (node (ref "C6") (pin "2") (pinfunction "2_2") (pintype "passive"))
      (node (ref "C7") (pin "2") (pinfunction "2_2") (pintype "passive"))
      (node (ref "C8") (pin "2") (pinfunction "2_2") (pintype "passive"))
      (node (ref "C9") (pin "1") (pinfunction "1_1") (pintype "passive"))
      (node (ref "D3") (pin "2") (pinfunction "GND_2") (pintype "bidirectional"))
      (node (ref "D4") (pin "1") (pinfunction "K_1") (pintype "bidirectional"))
      (node (ref "EPD_C1") (pin "2") (pinfunction "2_2") (pintype "passive"))
      (node (ref "EPD_C10") (pin "2") (pinfunction "2_2") (pintype "passive"))
      (node (ref "EPD_C11") (pin "2") (pinfunction "2_2") (pintype "passive"))
      (node (ref "EPD_C12") (pin "2") (pinfunction "2_2") (pintype "passive"))
      (node (ref "EPD_C2") (pin "2") (pinfunction "2_2") (pintype "passive"))
      (node (ref "EPD_C5") (pin "2") (pinfunction "2_2") (pintype "passive"))
      (node (ref "EPD_C6") (pin "2") (pinfunction "2_2") (pintype "passive"))
      (node (ref "EPD_C7") (pin "2") (pinfunction "2_2") (pintype "passive"))
      (node (ref "EPD_C8") (pin "2") (pinfunction "2_2") (pintype "passive"))
      (node (ref "EPD_C9") (pin "2") (pinfunction "2_2") (pintype "passive"))
      (node (ref "IC1") (pin "D2") (pinfunction "GND_D2") (pintype "bidirectional"))
      (node (ref "IC2") (pin "B1") (pinfunction "IN/TRIG_B1") (pintype "bidirectional"))
      (node (ref "IC2") (pin "B3") (pinfunction "GND_B3") (pintype "bidirectional"))
      (node (ref "IC3") (pin "8") (pinfunction "GNDIO_8") (pintype "bidirectional"))
      (node (ref "IC3") (pin "9") (pinfunction "GND_9") (pintype "bidirectional"))
      (node (ref "IC9") (pin "B1") (pinfunction "VSEL_B1") (pintype "bidirectional"))
      (node (ref "IC9") (pin "C1") (pinfunction "AGND_C1") (pintype "bidirectional"))
      (node (ref "IC9") (pin "C2") (pinfunction "PGND_1_C2") (pintype "bidirectional"))
      (node (ref "IC9") (pin "C3") (pinfunction "PGND_2_C3") (pintype "bidirectional"))
      (node (ref "J1") (pin "17") (pinfunction "17_17") (pintype "bidirectional"))
      (node (ref "J1") (pin "8") (pinfunction "8_8") (pintype "bidirectional"))
      (node (ref "J1") (pin "MP1") (pinfunction "MP1_MP1") (pintype "bidirectional"))
      (node (ref "J1") (pin "MP2") (pinfunction "MP2_MP2") (pintype "bidirectional"))
      (node (ref "J2") (pin "3") (pinfunction "3_3") (pintype "bidirectional"))
      (node (ref "J2") (pin "5") (pinfunction "5_5") (pintype "bidirectional"))
      (node (ref "J4") (pin "A12_B1") (pinfunction "GND_A12_B1") (pintype "power_in"))
      (node (ref "J4") (pin "A1_B12") (pinfunction "GND_A1_B12") (pintype "power_in"))
      (node (ref "J4") (pin "SH1") (pinfunction "SHIELD_SH1") (pintype "passive"))
      (node (ref "J4") (pin "SH2") (pinfunction "SHIELD_SH2") (pintype "passive"))
      (node (ref "J4") (pin "SH3") (pinfunction "SHIELD_SH3") (pintype "passive"))
      (node (ref "J4") (pin "SH4") (pinfunction "SHIELD_SH4") (pintype "passive"))
      (node (ref "R1_USB") (pin "1") (pinfunction "1_1") (pintype "bidirectional"))
      (node (ref "R2_EP_DR") (pin "1") (pinfunction "1_1") (pintype "bidirectional"))
      (node (ref "R2_USB") (pin "2") (pinfunction "2_2") (pintype "bidirectional"))
      (node (ref "R3") (pin "1") (pinfunction "1_1") (pintype "bidirectional"))
      (node (ref "R9") (pin "1") (pinfunction "1_1") (pintype "bidirectional"))
      (node (ref "R_TYPE_SEL") (pin "1") (pinfunction "1_1") (pintype "bidirectional"))
      (node (ref "SJ1") (pin "1") (pinfunction "1_1") (pintype "passive"))
      (node (ref "SW_DN") (pin "1") (pinfunction "1_1") (pintype "passive"))
      (node (ref "SW_ENT") (pin "1") (pinfunction "1_1") (pintype "passive"))
      (node (ref "SW_UP") (pin "1") (pinfunction "1_1") (pintype "passive"))
      (node (ref "TP_BAT_GND") (pin "TP") (pinfunction "TP_TP") (pintype "input"))
      (node (ref "TP_GND") (pin "TP") (pinfunction "TP_TP") (pintype "input"))
      (node (ref "U1") (pin "P$74") (pinfunction "VSS_PAD_P$74") (pintype "bidirectional"))
      (node (ref "U1") (pin "P$75") (pinfunction "VSS_PAD_P$75") (pintype "bidirectional"))
      (node (ref "U1") (pin "P$76") (pinfunction "VSS_PAD_P$76") (pintype "bidirectional"))
      (node (ref "U1") (pin "P$77") (pinfunction "VSS_PAD_P$77") (pintype "bidirectional"))
      (node (ref "U1") (pin "P$78") (pinfunction "VSS_PAD_P$78") (pintype "bidirectional"))
      (node (ref "U1") (pin "P$79") (pinfunction "VSS_PAD_P$79") (pintype "bidirectional"))
      (node (ref "U1") (pin "P$80") (pinfunction "VSS_PAD_P$80") (pintype "bidirectional"))
      (node (ref "U1") (pin "P$81") (pinfunction "VSS_PAD_P$81") (pintype "bidirectional"))
      (node (ref "U1") (pin "P$82") (pinfunction "VSS_PAD_P$82") (pintype "bidirectional"))
      (node (ref "U1") (pin "P$83") (pinfunction "VSS_PAD_P$83") (pintype "bidirectional"))
      (node (ref "U1") (pin "P$84") (pinfunction "VSS_PAD_P$84") (pintype "bidirectional"))
      (node (ref "U1") (pin "P$85") (pinfunction "VSS_PAD_P$85") (pintype "bidirectional"))
      (node (ref "U1") (pin "P$86") (pinfunction "VSS_PAD_P$86") (pintype "bidirectional"))
      (node (ref "U1") (pin "P$87") (pinfunction "VSS_PAD_P$87") (pintype "bidirectional"))
      (node (ref "U1") (pin "P$88") (pinfunction "VSS_PAD_P$88") (pintype "bidirectional"))
      (node (ref "U1") (pin "P$89") (pinfunction "VSS_PAD_P$89") (pintype "bidirectional"))
      (node (ref "U1") (pin "P$90") (pinfunction "VSS_PAD_P$90") (pintype "bidirectional"))
      (node (ref "U1") (pin "P$B7") (pinfunction "VSS_P$B7") (pintype "power_in"))
      (node (ref "U1") (pin "P$F23") (pinfunction "VSS_PA_P$F23") (pintype "bidirectional"))
      (node (ref "U3") (pin "1") (pinfunction "CTG_1") (pintype "power_in"))
      (node (ref "U3") (pin "4") (pinfunction "GND_4") (pintype "power_in"))
      (node (ref "U3") (pin "6") (pinfunction "QSTRT_6") (pintype "input"))
      (node (ref "U3") (pin "9") (pinfunction "EP_9") (pintype "power_in"))
      (node (ref "X1") (pin "2") (pinfunction "2_2") (pintype "passive"))
      (node (ref "X1") (pin "4") (pinfunction "4_4") (pintype "passive"))
    )
    (net (code "14") (name "HAPTIC_EN") (class "Default")
      (node (ref "IC2") (pin "A1") (pinfunction "EN_A1") (pintype "bidirectional"))
      (node (ref "U1") (pin "P$U1") (pinfunction "P0.12_P$U1") (pintype "bidirectional"))
    )
    (net (code "15") (name "IMU_INT1") (class "Default")
      (node (ref "IC3") (pin "5") (pinfunction "INT1_5") (pintype "bidirectional"))
      (node (ref "U1") (pin "P$N1") (pinfunction "P0.08_P$N1") (pintype "bidirectional"))
    )
    (net (code "16") (name "IMU_INT2") (class "Default")
      (node (ref "IC3") (pin "6") (pinfunction "INT2_6") (pintype "bidirectional"))
      (node (ref "U1") (pin "P$P2") (pinfunction "P1.08_P$P2") (pintype "bidirectional"))
    )
    (net (code "17") (name "LX1") (class "Default")
      (node (ref "IC9") (pin "B2") (pinfunction "SW1_1_B2") (pintype "bidirectional"))
      (node (ref "IC9") (pin "B3") (pinfunction "SW1_2_B3") (pintype "bidirectional"))
      (node (ref "L7") (pin "1") (pinfunction "1_1") (pintype "bidirectional"))
    )
    (net (code "18") (name "LX2") (class "Default")
      (node (ref "IC9") (pin "D2") (pinfunction "SW2_1_D2") (pintype "bidirectional"))
      (node (ref "IC9") (pin "D3") (pinfunction "SW2_2_D3") (pintype "bidirectional"))
      (node (ref "L7") (pin "2") (pinfunction "2_2") (pintype "bidirectional"))
    )
    (net (code "19") (name "MOSI") (class "Default")
      (node (ref "J1") (pin "14") (pinfunction "14_14") (pintype "bidirectional"))
      (node (ref "U1") (pin "P$B13") (pinfunction "P0.03/AIN1_P$B13") (pintype "bidirectional"))
    )
    (net (code "20") (name "Net-(ANT1-FEED)") (class "Default")
      (node (ref "ANT1") (pin "1") (pinfunction "FEED_1") (pintype "input"))
      (node (ref "C22") (pin "1") (pinfunction "1_1") (pintype "passive"))
      (node (ref "C4") (pin "1") (pinfunction "1_1") (pintype "passive"))
      (node (ref "L1") (pin "2") (pinfunction "2_2") (pintype "passive"))
    )
    (net (code "21") (name "Net-(D2-K)") (class "Default")
      (node (ref "C2-EP-DR") (pin "1") (pinfunction "1_1") (pintype "passive"))
      (node (ref "D2") (pin "1") (pinfunction "K_1") (pintype "bidirectional"))
      (node (ref "D4") (pin "2") (pinfunction "A_2") (pintype "bidirectional"))
    )
    (net (code "22") (name "Net-(D5-A)") (class "Default")
      (node (ref "C2-EP-DR") (pin "2") (pinfunction "2_2") (pintype "passive"))
      (node (ref "D5") (pin "2") (pinfunction "A_2") (pintype "bidirectional"))
      (node (ref "L5") (pin "1") (pinfunction "1_1") (pintype "passive"))
      (node (ref "Q3") (pin "3") (pinfunction "D_3") (pintype "bidirectional"))
    )
    (net (code "23") (name "Net-(EPD_C1-Pad1)") (class "Default")
      (node (ref "EPD_C1") (pin "1") (pinfunction "1_1") (pintype "passive"))
      (node (ref "J1") (pin "5") (pinfunction "5_5") (pintype "bidirectional"))
    )
    (net (code "24") (name "Net-(EPD_C2-Pad1)") (class "Default")
      (node (ref "EPD_C2") (pin "1") (pinfunction "1_1") (pintype "passive"))
      (node (ref "J1") (pin "4") (pinfunction "4_4") (pintype "bidirectional"))
    )
    (net (code "25") (name "Net-(EPD_C6-Pad1)") (class "Default")
      (node (ref "EPD_C6") (pin "1") (pinfunction "1_1") (pintype "passive"))
      (node (ref "J1") (pin "18") (pinfunction "18_18") (pintype "bidirectional"))
    )
    (net (code "26") (name "Net-(EPD_C7-Pad1)") (class "Default")
      (node (ref "EPD_C7") (pin "1") (pinfunction "1_1") (pintype "passive"))
      (node (ref "J1") (pin "19") (pinfunction "19_19") (pintype "bidirectional"))
    )
    (net (code "27") (name "Net-(EPD_C8-Pad1)") (class "Default")
      (node (ref "EPD_C8") (pin "1") (pinfunction "1_1") (pintype "passive"))
      (node (ref "J1") (pin "20") (pinfunction "20_20") (pintype "bidirectional"))
    )
    (net (code "28") (name "Net-(EPD_C10-Pad1)") (class "Default")
      (node (ref "EPD_C10") (pin "1") (pinfunction "1_1") (pintype "passive"))
      (node (ref "J1") (pin "22") (pinfunction "22_22") (pintype "bidirectional"))
    )
    (net (code "29") (name "Net-(EPD_C12-Pad1)") (class "Default")
      (node (ref "EPD_C12") (pin "1") (pinfunction "1_1") (pintype "passive"))
      (node (ref "J1") (pin "24") (pinfunction "24_24") (pintype "bidirectional"))
    )
    (net (code "30") (name "Net-(IC1-TS{slash}MR)") (class "Default")
      (node (ref "IC1") (pin "D1") (pinfunction "TS/MR_D1") (pintype "bidirectional"))
      (node (ref "R9") (pin "2") (pinfunction "2_2") (pintype "bidirectional"))
    )
    (net (code "31") (name "Net-(IC2-REG)") (class "Default")
      (node (ref "C32") (pin "2") (pinfunction "2_2") (pintype "passive"))
      (node (ref "IC2") (pin "A2") (pinfunction "REG_A2") (pintype "bidirectional"))
    )
    (net (code "32") (name "Net-(IC3-SDO)") (class "Default")
      (node (ref "IC3") (pin "1") (pinfunction "SDO_1") (pintype "bidirectional"))
      (node (ref "R3") (pin "2") (pinfunction "2_2") (pintype "bidirectional"))
    )
    (net (code "33") (name "Net-(IC9-SCL)") (class "Default")
      (node (ref "IC9") (pin "D1") (pinfunction "SCL_D1") (pintype "bidirectional"))
      (node (ref "R4") (pin "2") (pinfunction "2_2") (pintype "bidirectional"))
    )
    (net (code "34") (name "Net-(IC9-SDA)") (class "Default")
      (node (ref "IC9") (pin "E1") (pinfunction "SDA_E1") (pintype "bidirectional"))
      (node (ref "R2") (pin "2") (pinfunction "2_2") (pintype "bidirectional"))
    )
    (net (code "35") (name "Net-(J4-CC1)") (class "Default")
      (node (ref "J4") (pin "A5") (pinfunction "CC1_A5") (pintype "bidirectional"))
      (node (ref "R1_USB") (pin "2") (pinfunction "2_2") (pintype "bidirectional"))
    )
    (net (code "36") (name "Net-(J4-CC2)") (class "Default")
      (node (ref "J4") (pin "B5") (pinfunction "CC2_B5") (pintype "bidirectional"))
      (node (ref "R2_USB") (pin "1") (pinfunction "1_1") (pintype "bidirectional"))
    )
    (net (code "37") (name "Net-(L2-Pad2)") (class "Default")
      (node (ref "L2") (pin "2") (pinfunction "2_2") (pintype "passive"))
      (node (ref "L3") (pin "1") (pinfunction "1_1") (pintype "passive"))
    )
    (net (code "38") (name "Net-(R1_EP_DR-Pad1)") (class "Default")
      (node (ref "R1_EP_DR") (pin "1") (pinfunction "1_1") (pintype "bidirectional"))
      (node (ref "R_TYPE_SEL") (pin "2") (pinfunction "2_2") (pintype "bidirectional"))
      (node (ref "SJ1") (pin "2") (pinfunction "2_2") (pintype "passive"))
    )
    (net (code "39") (name "Net-(U1-ANT)") (class "Default")
      (node (ref "C3") (pin "1") (pinfunction "1_1") (pintype "passive"))
      (node (ref "L1") (pin "1") (pinfunction "1_1") (pintype "passive"))
      (node (ref "U1") (pin "P$H23") (pinfunction "ANT_P$H23") (pintype "bidirectional"))
    )
    (net (code "40") (name "Net-(U1-DCC)") (class "Default")
      (node (ref "L2") (pin "1") (pinfunction "1_1") (pintype "passive"))
      (node (ref "U1") (pin "P$B3") (pinfunction "DCC_P$B3") (pintype "output"))
    )
    (net (code "41") (name "Net-(U1-DEC1)") (class "Default")
      (node (ref "C5") (pin "1") (pinfunction "1_1") (pintype "passive"))
      (node (ref "U1") (pin "P$C1") (pinfunction "DEC1_P$C1") (pintype "power_in"))
    )
    (net (code "42") (name "Net-(U1-DEC2)") (class "Default")
      (node (ref "C13") (pin "1") (pinfunction "1_1") (pintype "passive"))
      (node (ref "U1") (pin "P$A18") (pinfunction "DEC2_P$A18") (pintype "bidirectional"))
    )
    (net (code "43") (name "Net-(U1-DEC3)") (class "Default")
      (node (ref "C11") (pin "1") (pinfunction "1_1") (pintype "passive"))
      (node (ref "U1") (pin "P$D23") (pinfunction "DEC3_P$D23") (pintype "bidirectional"))
    )
    (net (code "44") (name "Net-(U1-DEC3V3)") (class "Default")
      (node (ref "C20") (pin "1") (pinfunction "1_1") (pintype "passive"))
      (node (ref "U1") (pin "P$AC5") (pinfunction "DEC3V3_P$AC5") (pintype "bidirectional"))
    )
    (net (code "45") (name "Net-(U1-DEC4)") (class "Default")
      (node (ref "C10") (pin "1") (pinfunction "1_1") (pintype "passive"))
      (node (ref "C15") (pin "1") (pinfunction "1_1") (pintype "passive"))
      (node (ref "C16") (pin "1") (pinfunction "1_1") (pintype "passive"))
      (node (ref "L3") (pin "2") (pinfunction "2_2") (pintype "passive"))
      (node (ref "U1") (pin "P$B5") (pinfunction "DEC4_P$B5") (pintype "power_in"))
      (node (ref "U1") (pin "P$E24") (pinfunction "DEC6_P$E24") (pintype "bidirectional"))
    )
    (net (code "46") (name "Net-(U1-DEC5)") (class "Default")
      (node (ref "C9") (pin "2") (pinfunction "2_2") (pintype "passive"))
      (node (ref "U1") (pin "P$N24") (pinfunction "DEC5_P$N24") (pintype "bidirectional"))
    )
    (net (code "47") (name "Net-(U1-P0.00{slash}XL1)") (class "Default")
      (node (ref "C17") (pin "2") (pinfunction "2_2") (pintype "passive"))
      (node (ref "U1") (pin "P$D2") (pinfunction "P0.00/XL1_P$D2") (pintype "bidirectional"))
      (node (ref "X2") (pin "1") (pinfunction "1_1") (pintype "passive"))
    )
    (net (code "48") (name "Net-(U1-P0.01{slash}XL2)") (class "Default")
      (node (ref "C18") (pin "2") (pinfunction "2_2") (pintype "passive"))
      (node (ref "U1") (pin "P$F2") (pinfunction "P0.01/XL2_P$F2") (pintype "bidirectional"))
      (node (ref "X2") (pin "2") (pinfunction "2_2") (pintype "passive"))
    )
    (net (code "49") (name "Net-(U1-XC1)") (class "Default")
      (node (ref "C1") (pin "1") (pinfunction "1_1") (pintype "passive"))
      (node (ref "U1") (pin "P$B24") (pinfunction "XC1_P$B24") (pintype "input"))
      (node (ref "X1") (pin "1") (pinfunction "1_1") (pintype "passive"))
    )
    (net (code "50") (name "Net-(U1-XC2)") (class "Default")
      (node (ref "C2") (pin "1") (pinfunction "1_1") (pintype "passive"))
      (node (ref "U1") (pin "P$A23") (pinfunction "XC2_P$A23") (pintype "output"))
      (node (ref "X1") (pin "3") (pinfunction "3_3") (pintype "passive"))
    )
    (net (code "51") (name "OUT+") (class "Default")
      (node (ref "IC2") (pin "A3") (pinfunction "OUT+_A3") (pintype "bidirectional"))
      (node (ref "TP_OP") (pin "TP") (pinfunction "TP_TP") (pintype "input"))
    )
    (net (code "52") (name "OUT-") (class "Default")
      (node (ref "IC2") (pin "C3") (pinfunction "OUT-_C3") (pintype "bidirectional"))
      (node (ref "TP_ON") (pin "TP") (pinfunction "TP_TP") (pintype "input"))
    )
    (net (code "53") (name "P0.04") (class "Default")
      (node (ref "U1") (pin "P$J1") (pinfunction "P0.04/AIN2_P$J1") (pintype "bidirectional"))
    )
    (net (code "54") (name "P0.09") (class "Default")
      (node (ref "U1") (pin "P$L24") (pinfunction "P0.09/NFC1_P$L24") (pintype "bidirectional"))
    )
    (net (code "55") (name "P0.13") (class "Default")
      (node (ref "C30") (pin "2") (pinfunction "2_2") (pintype "passive"))
      (node (ref "R5") (pin "1") (pinfunction "1_1") (pintype "bidirectional"))
      (node (ref "SW_UP") (pin "2") (pinfunction "2_2") (pintype "passive"))
      (node (ref "U1") (pin "P$AD8") (pinfunction "P0.13_P$AD8") (pintype "bidirectional"))
    )
    (net (code "56") (name "P0.14") (class "Default")
      (node (ref "C31") (pin "2") (pinfunction "2_2") (pintype "passive"))
      (node (ref "R8") (pin "1") (pinfunction "1_1") (pintype "bidirectional"))
      (node (ref "SW_ENT") (pin "2") (pinfunction "2_2") (pintype "passive"))
      (node (ref "U1") (pin "P$AC9") (pinfunction "P0.14_P$AC9") (pintype "bidirectional"))
    )
    (net (code "57") (name "P0.19") (class "Default")
      (node (ref "U1") (pin "P$AC15") (pinfunction "P0.19_P$AC15") (pintype "bidirectional"))
    )
    (net (code "58") (name "P0.20") (class "Default")
      (node (ref "U1") (pin "P$AD16") (pinfunction "P0.20_P$AD16") (pintype "bidirectional"))
    )
    (net (code "59") (name "P0.21") (class "Default")
      (node (ref "U1") (pin "P$AC17") (pinfunction "P0.21_P$AC17") (pintype "bidirectional"))
    )
    (net (code "60") (name "P0.22") (class "Default")
      (node (ref "U1") (pin "P$AD18") (pinfunction "P0.22_P$AD18") (pintype "bidirectional"))
    )
    (net (code "61") (name "P0.23") (class "Default")
      (node (ref "U1") (pin "P$AC19") (pinfunction "P0.23_P$AC19") (pintype "bidirectional"))
    )
    (net (code "62") (name "P0.24") (class "Default")
      (node (ref "U1") (pin "P$AD20") (pinfunction "P0.24_P$AD20") (pintype "bidirectional"))
    )
    (net (code "63") (name "P0.25") (class "Default")
      (node (ref "U1") (pin "P$AC21") (pinfunction "P0.25_P$AC21") (pintype "bidirectional"))
    )
    (net (code "64") (name "P0.26") (class "Default")
      (node (ref "U1") (pin "P$G1") (pinfunction "P0.26_P$G1") (pintype "bidirectional"))
    )
    (net (code "65") (name "P0.27") (class "Default")
      (node (ref "U1") (pin "P$H2") (pinfunction "P0.27_P$H2") (pintype "bidirectional"))
    )
    (net (code "66") (name "P0.28") (class "Default")
      (node (ref "U1") (pin "P$B11") (pinfunction "P0.28/AIN4_P$B11") (pintype "bidirectional"))
    )
    (net (code "67") (name "P0.29") (class "Default")
      (node (ref "U1") (pin "P$A10") (pinfunction "P0.29/AIN5_P$A10") (pintype "bidirectional"))
    )
    (net (code "68") (name "P0.30") (class "Default")
      (node (ref "U1") (pin "P$B9") (pinfunction "P0.30/AIN6_P$B9") (pintype "bidirectional"))
    )
    (net (code "69") (name "P0.31") (class "Default")
      (node (ref "U1") (pin "P$A8") (pinfunction "P0.31/AIN7_P$A8") (pintype "bidirectional"))
    )
    (net (code "70") (name "P1.01") (class "Default")
      (node (ref "Q1") (pin "1") (pinfunction "G_1") (pintype "bidirectional"))
      (node (ref "R_PWR_EPD") (pin "1") (pinfunction "1_1") (pintype "bidirectional"))
      (node (ref "U1") (pin "P$Y23") (pinfunction "P1.01_P$Y23") (pintype "bidirectional"))
    )
    (net (code "71") (name "P1.02") (class "Default")
      (node (ref "C29") (pin "2") (pinfunction "2_2") (pintype "passive"))
      (node (ref "R7") (pin "1") (pinfunction "1_1") (pintype "bidirectional"))
      (node (ref "SW_DN") (pin "2") (pinfunction "2_2") (pintype "passive"))
      (node (ref "U1") (pin "P$W24") (pinfunction "P1.02_P$W24") (pintype "bidirectional"))
    )
    (net (code "72") (name "P1.03") (class "Default")
      (node (ref "U1") (pin "P$V23") (pinfunction "P1.03_P$V23") (pintype "bidirectional"))
    )
    (net (code "73") (name "P1.04") (class "Default")
      (node (ref "U1") (pin "P$U24") (pinfunction "P1.04_P$U24") (pintype "bidirectional"))
    )
    (net (code "74") (name "P1.05") (class "Default")
      (node (ref "U1") (pin "P$T23") (pinfunction "P1.05_P$T23") (pintype "bidirectional"))
    )
    (net (code "75") (name "P1.06") (class "Default")
      (node (ref "U1") (pin "P$R24") (pinfunction "P1.06_P$R24") (pintype "bidirectional"))
    )
    (net (code "76") (name "P1.07") (class "Default")
      (node (ref "U1") (pin "P$P23") (pinfunction "P1.07_P$P23") (pintype "bidirectional"))
    )
    (net (code "77") (name "P1.09") (class "Default")
      (node (ref "U1") (pin "P$R1") (pinfunction "P1.09_P$R1") (pintype "bidirectional"))
    )
    (net (code "78") (name "P1.10") (class "Default")
      (node (ref "U1") (pin "P$A20") (pinfunction "P1.10_P$A20") (pintype "bidirectional"))
    )
    (net (code "79") (name "P1.11") (class "Default")
      (node (ref "U1") (pin "P$B19") (pinfunction "P1.11_P$B19") (pintype "bidirectional"))
    )
    (net (code "80") (name "P1.12") (class "Default")
      (node (ref "U1") (pin "P$B17") (pinfunction "P1.12_P$B17") (pintype "bidirectional"))
    )
    (net (code "81") (name "P1.13") (class "Default")
      (node (ref "U1") (pin "P$A16") (pinfunction "P1.13_P$A16") (pintype "bidirectional"))
    )
    (net (code "82") (name "P1.14") (class "Default")
      (node (ref "U1") (pin "P$B15") (pinfunction "P1.14_P$B15") (pintype "bidirectional"))
    )
    (net (code "83") (name "P1.15") (class "Default")
      (node (ref "U1") (pin "P$A14") (pinfunction "P1.15_P$A14") (pintype "bidirectional"))
    )
    (net (code "84") (name "PMIC_INT") (class "Default")
      (node (ref "IC1") (pin "A1") (pinfunction "~{INT}_A1") (pintype "bidirectional"))
      (node (ref "U1") (pin "P$T2") (pinfunction "P0.11_P$T2") (pintype "bidirectional"))
    )
    (net (code "85") (name "PREVGH") (class "Default")
      (node (ref "D5") (pin "1") (pinfunction "K_1") (pintype "bidirectional"))
      (node (ref "EPD_C9") (pin "1") (pinfunction "1_1") (pintype "passive"))
      (node (ref "J1") (pin "21") (pinfunction "21_21") (pintype "bidirectional"))
    )
    (net (code "86") (name "PREVGL") (class "Default")
      (node (ref "D2") (pin "2") (pinfunction "A_2") (pintype "bidirectional"))
      (node (ref "EPD_C11") (pin "1") (pinfunction "1_1") (pintype "passive"))
      (node (ref "J1") (pin "23") (pinfunction "23_23") (pintype "bidirectional"))
    )
    (net (code "87") (name "RESE") (class "Default")
      (node (ref "J1") (pin "3") (pinfunction "3_3") (pintype "bidirectional"))
      (node (ref "Q3") (pin "2") (pinfunction "S_2") (pintype "bidirectional"))
      (node (ref "R1_EP_DR") (pin "2") (pinfunction "2_2") (pintype "bidirectional"))
    )
    (net (code "88") (name "RESET") (class "Default")
      (node (ref "J2") (pin "6") (pinfunction "6_6") (pintype "bidirectional"))
      (node (ref "TP_RESET") (pin "TP") (pinfunction "TP_TP") (pintype "input"))
      (node (ref "U1") (pin "P$AC13") (pinfunction "P0.18/RESET_P$AC13") (pintype "bidirectional"))
    )
    (net (code "89") (name "SCK") (class "Default")
      (node (ref "J1") (pin "13") (pinfunction "13_13") (pintype "bidirectional"))
      (node (ref "U1") (pin "P$A12") (pinfunction "P0.02/AIN0_P$A12") (pintype "bidirectional"))
    )
    (net (code "90") (name "SCL") (class "Default")
      (node (ref "IC1") (pin "B1") (pinfunction "SCL_B1") (pintype "bidirectional"))
      (node (ref "IC2") (pin "C1") (pinfunction "SCL_C1") (pintype "bidirectional"))
      (node (ref "IC3") (pin "12") (pinfunction "SCX_12") (pintype "bidirectional"))
      (node (ref "R17") (pin "2") (pinfunction "2_2") (pintype "bidirectional"))
      (node (ref "R4") (pin "1") (pinfunction "1_1") (pintype "bidirectional"))
      (node (ref "TP_SCL") (pin "TP") (pinfunction "TP_TP") (pintype "input"))
      (node (ref "U1") (pin "P$M2") (pinfunction "P0.07_P$M2") (pintype "bidirectional"))
      (node (ref "U3") (pin "7") (pinfunction "SCL_7") (pintype "input"))
    )
    (net (code "91") (name "SDA") (class "Default")
      (node (ref "IC1") (pin "C1") (pinfunction "SDA_C1") (pintype "bidirectional"))
      (node (ref "IC2") (pin "B2") (pinfunction "SDA_B2") (pintype "bidirectional"))
      (node (ref "IC3") (pin "2") (pinfunction "SDX_2") (pintype "bidirectional"))
      (node (ref "R18") (pin "2") (pinfunction "2_2") (pintype "bidirectional"))
      (node (ref "R2") (pin "1") (pinfunction "1_1") (pintype "bidirectional"))
      (node (ref "TP_SDA") (pin "TP") (pinfunction "TP_TP") (pintype "input"))
      (node (ref "U1") (pin "P$L1") (pinfunction "P0.06_P$L1") (pintype "bidirectional"))
      (node (ref "U3") (pin "8") (pinfunction "SDA_8") (pintype "bidirectional"))
    )
    (net (code "92") (name "SWDCLK") (class "Default")
      (node (ref "J2") (pin "4") (pinfunction "4_4") (pintype "bidirectional"))
      (node (ref "TP_SWDCLK") (pin "TP") (pinfunction "TP_TP") (pintype "input"))
      (node (ref "U1") (pin "P$AA24") (pinfunction "SWDCLK_P$AA24") (pintype "input"))
    )
    (net (code "93") (name "SWDIO") (class "Default")
      (node (ref "J2") (pin "2") (pinfunction "2_2") (pintype "bidirectional"))
      (node (ref "TP_SWDIO") (pin "TP") (pinfunction "TP_TP") (pintype "input"))
      (node (ref "U1") (pin "P$AC24") (pinfunction "SWDIO_P$AC24") (pintype "bidirectional"))
    )
    (net (code "94") (name "SWO") (class "Default")
      (node (ref "TP_SWO") (pin "TP") (pinfunction "TP_TP") (pintype "input"))
      (node (ref "U1") (pin "P$AD22") (pinfunction "P1.00_P$AD22") (pintype "bidirectional"))
    )
    (net (code "95") (name "VBAT") (class "Default")
      (node (ref "C27") (pin "2") (pinfunction "2_2") (pintype "passive"))
      (node (ref "C37") (pin "2") (pinfunction "2_2") (pintype "passive"))
      (node (ref "IC1") (pin "C2") (pinfunction "BAT_C2") (pintype "bidirectional"))
      (node (ref "TP_VBAT") (pin "TP") (pinfunction "TP_TP") (pintype "input"))
      (node (ref "U3") (pin "2") (pinfunction "CELL_2") (pintype "power_in"))
      (node (ref "U3") (pin "3") (pinfunction "VDD_3") (pintype "power_in"))
    )
    (net (code "96") (name "VBUS") (class "Default")
      (node (ref "C21") (pin "1") (pinfunction "1_1") (pintype "passive"))
      (node (ref "C38") (pin "2") (pinfunction "2_2") (pintype "passive"))
      (node (ref "C42") (pin "1") (pinfunction "1_1") (pintype "passive"))
      (node (ref "C43") (pin "1") (pinfunction "1_1") (pintype "passive"))
      (node (ref "D3") (pin "5") (pinfunction "VBUS_5") (pintype "bidirectional"))
      (node (ref "IC1") (pin "A2") (pinfunction "IN_A2") (pintype "bidirectional"))
      (node (ref "J4") (pin "A4_B9") (pinfunction "VBUS_A4_B9") (pintype "power_in"))
      (node (ref "J4") (pin "A9_B4") (pinfunction "VBUS_A9_B4") (pintype "power_in"))
      (node (ref "U1") (pin "P$AD2") (pinfunction "VBUS_P$AD2") (pintype "power_in"))
    )
    (net (code "97") (name "VREG") (class "Default")
      (node (ref "C23") (pin "2") (pinfunction "2_2") (pintype "passive"))
      (node (ref "C24") (pin "2") (pinfunction "2_2") (pintype "passive"))
      (node (ref "C39") (pin "2") (pinfunction "2_2") (pintype "passive"))
      (node (ref "IC1") (pin "B2") (pinfunction "SYS_B2") (pintype "bidirectional"))
      (node (ref "IC9") (pin "A1") (pinfunction "EN_A1") (pintype "bidirectional"))
      (node (ref "IC9") (pin "A2") (pinfunction "VIN_1_A2") (pintype "bidirectional"))
      (node (ref "IC9") (pin "A3") (pinfunction "VIN_2_A3") (pintype "bidirectional"))
      (node (ref "TP_VREG") (pin "TP") (pinfunction "TP_TP") (pintype "input"))
    )
    (net (code "98") (name "unconnected-(ANT1-NC-Pad2)") (class "Default")
      (node (ref "ANT1") (pin "2") (pinfunction "NC_2") (pintype "no_connect"))
    )
    (net (code "99") (name "unconnected-(IC3-ASCL-Pad11)") (class "Default")
      (node (ref "IC3") (pin "11") (pinfunction "ASCL_11") (pintype "bidirectional"))
    )
    (net (code "100") (name "unconnected-(IC3-ASDA-Pad4)") (class "Default")
      (node (ref "IC3") (pin "4") (pinfunction "ASDA_4") (pintype "bidirectional"))
    )
    (net (code "101") (name "unconnected-(J1-Pad1)") (class "Default")
      (node (ref "J1") (pin "1") (pinfunction "1_1") (pintype "bidirectional"))
    )
    (net (code "102") (name "unconnected-(J1-Pad6)") (class "Default")
      (node (ref "J1") (pin "6") (pinfunction "6_6") (pintype "bidirectional"))
    )
    (net (code "103") (name "unconnected-(J1-Pad7)") (class "Default")
      (node (ref "J1") (pin "7") (pinfunction "7_7") (pintype "bidirectional"))
    )
    (net (code "104") (name "unconnected-(J4-SBU1-PadA8)") (class "Default")
      (node (ref "J4") (pin "A8") (pinfunction "SBU1_A8") (pintype "bidirectional"))
    )
    (net (code "105") (name "unconnected-(J4-SBU2-PadB8)") (class "Default")
      (node (ref "J4") (pin "B8") (pinfunction "SBU2_B8") (pintype "bidirectional"))
    )
    (net (code "106") (name "unconnected-(U1-DCCH-PadP$AB2)") (class "Default")
      (node (ref "U1") (pin "P$AB2") (pinfunction "DCCH_P$AB2") (pintype "bidirectional"))
    )
  )
)
